# timelapse3fixes.net
KiCad netlist of a schematic drawn in EAGLE
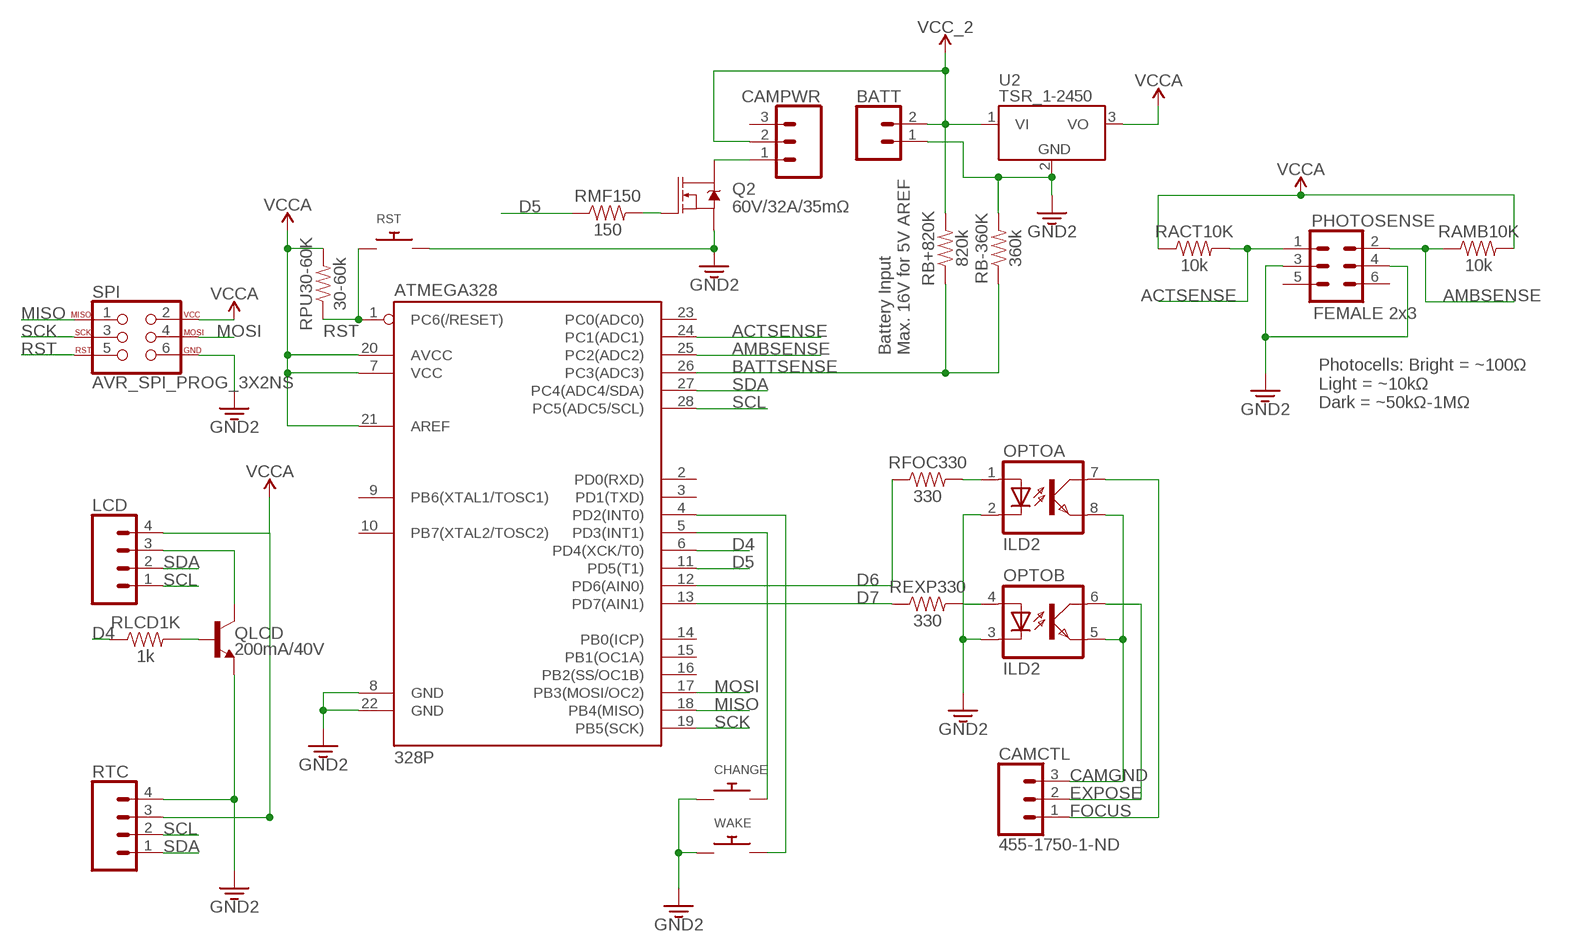
[diagram p0: schematic, sheet 1]

(export (version "E")
  (design (tool "Eeschema 10.0.6"))
  (components
    (comp (ref "ATMEGA328")
      (value "328P")
      (footprint "eagle-import:DIP28")
      (libsource (lib "eagle-import") (part "ATMEGA328P_PDIP"))
    )
    (comp (ref "BATT")
      (value "CONN_02")
      (footprint "eagle-import:1X02")
      (libsource (lib "eagle-import") (part "CONN_02"))
    )
    (comp (ref "CAMCTL")
      (value "455-1750-1-ND")
      (footprint "eagle-import:1X03")
      (libsource (lib "eagle-import") (part "CONN_03"))
    )
    (comp (ref "CAMPWR")
      (value "CONN_03")
      (footprint "eagle-import:1X03")
      (libsource (lib "eagle-import") (part "CONN_03"))
    )
    (comp (ref "CHANGE")
      (value "SWITCH_PUSHBUTTONEVQ-PE")
      (footprint "eagle-import:TACT_PANA-EVQ")
      (libsource (lib "eagle-import") (part "SWITCH_PUSHBUTTONEVQ-PE"))
    )
    (comp (ref "LCD")
      (value "CONN_04")
      (footprint "eagle-import:1X04")
      (libsource (lib "eagle-import") (part "CONN_04"))
    )
    (comp (ref "OPTO")
      (value "ILD2")
      (footprint "eagle-import:DIL08")
      (libsource (lib "eagle-import") (part "ILD2"))
    )
    (comp (ref "PHOTOSENSE")
      (value "FEMALE 2x3")
      (footprint "eagle-import:2X3")
      (libsource (lib "eagle-import") (part "CONN_03X2FEMALE"))
    )
    (comp (ref "Q2")
      (value "60V/32A/35mΩ")
      (footprint "eagle-import:TO220V")
      (libsource (lib "eagle-import") (part "MOSFET-NCH-FQP30N06L"))
    )
    (comp (ref "QLCD")
      (value "200mA/40V")
      (footprint "eagle-import:TO-92")
      (libsource (lib "eagle-import") (part "TRANS_NPN-2N3904"))
    )
    (comp (ref "RACT10K")
      (value "10k")
      (footprint "eagle-import:AXIAL-0.3")
      (libsource (lib "eagle-import") (part "10KOHM-HORIZ-1/4W-1%"))
    )
    (comp (ref "RAMB10K")
      (value "10k")
      (footprint "eagle-import:AXIAL-0.3")
      (libsource (lib "eagle-import") (part "10KOHM-HORIZ-1/4W-1%"))
    )
    (comp (ref "RB+820K")
      (value "820k")
      (footprint "eagle-import:AXIAL-0.3")
      (libsource (lib "eagle-import") (part "10KOHM-HORIZ-1/4W-1%"))
    )
    (comp (ref "RB-360K")
      (value "360k")
      (footprint "eagle-import:AXIAL-0.3")
      (libsource (lib "eagle-import") (part "10KOHM-HORIZ-1/4W-1%"))
    )
    (comp (ref "REXP330")
      (value "330")
      (footprint "eagle-import:AXIAL-0.3")
      (libsource (lib "eagle-import") (part "330OHM-HORIZ-1/10W-5%"))
    )
    (comp (ref "RFOC330")
      (value "330")
      (footprint "eagle-import:AXIAL-0.3")
      (libsource (lib "eagle-import") (part "330OHM-HORIZ-1/10W-5%"))
    )
    (comp (ref "RLCD1K")
      (value "1k")
      (footprint "eagle-import:AXIAL-0.3")
      (libsource (lib "eagle-import") (part "330OHM-HORIZ-1/10W-5%"))
    )
    (comp (ref "RMF150")
      (value "150")
      (footprint "eagle-import:AXIAL-0.3")
      (libsource (lib "eagle-import") (part "330OHM-HORIZ-1/10W-5%"))
    )
    (comp (ref "RPU30-60K")
      (value "30-60k")
      (footprint "eagle-import:AXIAL-0.3")
      (libsource (lib "eagle-import") (part "330OHM-HORIZ-1/10W-5%"))
    )
    (comp (ref "RST")
      (value "SWITCH_PUSHBUTTONEVQ-PE")
      (footprint "eagle-import:TACT_PANA-EVQ")
      (libsource (lib "eagle-import") (part "SWITCH_PUSHBUTTONEVQ-PE"))
    )
    (comp (ref "RTC")
      (value "CONN_04")
      (footprint "eagle-import:1X04")
      (libsource (lib "eagle-import") (part "CONN_04"))
    )
    (comp (ref "SPI")
      (value "AVR_SPI_PROG_3X2NS")
      (footprint "eagle-import:2X3-NS")
      (libsource (lib "eagle-import") (part "AVR_SPI_PROG_3X2NS"))
    )
    (comp (ref "U2")
      (value "TSR_1-2450")
      (footprint "eagle-import:TSR-1")
      (libsource (lib "eagle-import") (part "TSR_1-2450"))
    )
    (comp (ref "WAKE")
      (value "SWITCH_PUSHBUTTONEVQ-PE")
      (footprint "eagle-import:TACT_PANA-EVQ")
      (libsource (lib "eagle-import") (part "SWITCH_PUSHBUTTONEVQ-PE"))
    )
  )
  (nets
    (net (code "1") (name "/ACTSENSE") (class "Default")
      (node (ref "ATMEGA328") (pin "24") (pinfunction "PC1(ADC1)_24") (pintype "bidirectional"))
      (node (ref "PHOTOSENSE") (pin "1") (pinfunction "1_1") (pintype "bidirectional"))
      (node (ref "RACT10K") (pin "P$2") (pinfunction "2_P$2") (pintype "passive"))
    )
    (net (code "2") (name "/AMBSENSE") (class "Default")
      (node (ref "ATMEGA328") (pin "25") (pinfunction "PC2(ADC2)_25") (pintype "bidirectional"))
      (node (ref "PHOTOSENSE") (pin "2") (pinfunction "2_2") (pintype "bidirectional"))
      (node (ref "RAMB10K") (pin "P$1") (pinfunction "1_P$1") (pintype "passive"))
    )
    (net (code "3") (name "/BATTSENSE") (class "Default")
      (node (ref "ATMEGA328") (pin "26") (pinfunction "PC3(ADC3)_26") (pintype "bidirectional"))
      (node (ref "RB+820K") (pin "P$1") (pinfunction "1_P$1") (pintype "passive"))
      (node (ref "RB-360K") (pin "P$1") (pinfunction "1_P$1") (pintype "passive"))
    )
    (net (code "4") (name "/CAMGND") (class "Default")
      (node (ref "CAMCTL") (pin "3") (pinfunction "3_3") (pintype "passive"))
      (node (ref "OPTO") (pin "5") (pinfunction "EMIT_5") (pintype "passive"))
      (node (ref "OPTO") (pin "8") (pinfunction "EMIT_8") (pintype "passive"))
    )
    (net (code "5") (name "/D4") (class "Default")
      (node (ref "ATMEGA328") (pin "6") (pinfunction "PD4(XCK/T0)_6") (pintype "bidirectional"))
      (node (ref "RLCD1K") (pin "P$1") (pinfunction "1_P$1") (pintype "passive"))
    )
    (net (code "6") (name "/D5") (class "Default")
      (node (ref "ATMEGA328") (pin "11") (pinfunction "PD5(T1)_11") (pintype "bidirectional"))
      (node (ref "RMF150") (pin "P$1") (pinfunction "1_P$1") (pintype "passive"))
    )
    (net (code "7") (name "/D6") (class "Default")
      (node (ref "ATMEGA328") (pin "12") (pinfunction "PD6(AIN0)_12") (pintype "bidirectional"))
      (node (ref "RFOC330") (pin "P$1") (pinfunction "1_P$1") (pintype "passive"))
    )
    (net (code "8") (name "/D7") (class "Default")
      (node (ref "ATMEGA328") (pin "13") (pinfunction "PD7(AIN1)_13") (pintype "bidirectional"))
      (node (ref "REXP330") (pin "P$1") (pinfunction "1_P$1") (pintype "passive"))
    )
    (net (code "9") (name "/EXPOSE") (class "Default")
      (node (ref "CAMCTL") (pin "2") (pinfunction "2_2") (pintype "passive"))
      (node (ref "OPTO") (pin "6") (pinfunction "COL_6") (pintype "passive"))
    )
    (net (code "10") (name "/FOCUS") (class "Default")
      (node (ref "CAMCTL") (pin "1") (pinfunction "1_1") (pintype "passive"))
      (node (ref "OPTO") (pin "7") (pinfunction "COL_7") (pintype "passive"))
    )
    (net (code "11") (name "/MISO") (class "Default")
      (node (ref "ATMEGA328") (pin "18") (pinfunction "PB4(MISO)_18") (pintype "bidirectional"))
      (node (ref "SPI") (pin "1") (pinfunction "1_1") (pintype "passive"))
    )
    (net (code "12") (name "/MOSI") (class "Default")
      (node (ref "ATMEGA328") (pin "17") (pinfunction "PB3(MOSI/OC2)_17") (pintype "bidirectional"))
      (node (ref "SPI") (pin "4") (pinfunction "4_4") (pintype "passive"))
    )
    (net (code "13") (name "/RST") (class "Default")
      (node (ref "ATMEGA328") (pin "1") (pinfunction "PC6(/RESET)_1") (pintype "bidirectional"))
      (node (ref "RPU30-60K") (pin "P$1") (pinfunction "1_P$1") (pintype "passive"))
      (node (ref "RST") (pin "P$1") (pinfunction "P$1_P$1") (pintype "passive"))
      (node (ref "SPI") (pin "5") (pinfunction "5_5") (pintype "passive"))
    )
    (net (code "14") (name "/SCK") (class "Default")
      (node (ref "ATMEGA328") (pin "19") (pinfunction "PB5(SCK)_19") (pintype "bidirectional"))
      (node (ref "SPI") (pin "3") (pinfunction "3_3") (pintype "passive"))
    )
    (net (code "15") (name "/SCL") (class "Default")
      (node (ref "ATMEGA328") (pin "28") (pinfunction "PC5(ADC5/SCL)_28") (pintype "bidirectional"))
      (node (ref "LCD") (pin "1") (pinfunction "1_1") (pintype "passive"))
      (node (ref "RTC") (pin "2") (pinfunction "2_2") (pintype "passive"))
    )
    (net (code "16") (name "/SDA") (class "Default")
      (node (ref "ATMEGA328") (pin "27") (pinfunction "PC4(ADC4/SDA)_27") (pintype "bidirectional"))
      (node (ref "LCD") (pin "2") (pinfunction "2_2") (pintype "passive"))
      (node (ref "RTC") (pin "1") (pinfunction "1_1") (pintype "passive"))
    )
    (net (code "17") (name "GND2") (class "Default")
      (node (ref "ATMEGA328") (pin "22") (pinfunction "GND_22") (pintype "bidirectional"))
      (node (ref "ATMEGA328") (pin "8") (pinfunction "GND_8") (pintype "bidirectional"))
      (node (ref "BATT") (pin "1") (pinfunction "1_1") (pintype "passive"))
      (node (ref "CHANGE") (pin "P$1") (pinfunction "P$1_P$1") (pintype "passive"))
      (node (ref "OPTO") (pin "2") (pinfunction "C_2") (pintype "passive"))
      (node (ref "OPTO") (pin "3") (pinfunction "C_3") (pintype "passive"))
      (node (ref "PHOTOSENSE") (pin "3") (pinfunction "3_3") (pintype "bidirectional"))
      (node (ref "PHOTOSENSE") (pin "4") (pinfunction "4_4") (pintype "bidirectional"))
      (node (ref "Q2") (pin "3") (pinfunction "S_3") (pintype "bidirectional"))
      (node (ref "QLCD") (pin "1") (pinfunction "E_1") (pintype "passive"))
      (node (ref "RB-360K") (pin "P$2") (pinfunction "2_P$2") (pintype "passive"))
      (node (ref "RST") (pin "P$2") (pinfunction "P$2_P$2") (pintype "passive"))
      (node (ref "RTC") (pin "4") (pinfunction "4_4") (pintype "passive"))
      (node (ref "SPI") (pin "6") (pinfunction "6_6") (pintype "passive"))
      (node (ref "U2") (pin "2") (pinfunction "GND_2") (pintype "power_in"))
      (node (ref "WAKE") (pin "P$1") (pinfunction "P$1_P$1") (pintype "passive"))
    )
    (net (code "18") (name "Net-(ATMEGA328-PD2(INT0))") (class "Default")
      (node (ref "ATMEGA328") (pin "4") (pinfunction "PD2(INT0)_4") (pintype "bidirectional"))
      (node (ref "WAKE") (pin "P$2") (pinfunction "P$2_P$2") (pintype "passive"))
    )
    (net (code "19") (name "Net-(ATMEGA328-PD3(INT1))") (class "Default")
      (node (ref "ATMEGA328") (pin "5") (pinfunction "PD3(INT1)_5") (pintype "bidirectional"))
      (node (ref "CHANGE") (pin "P$2") (pinfunction "P$2_P$2") (pintype "passive"))
    )
    (net (code "20") (name "Net-(OPTOA-A)") (class "Default")
      (node (ref "OPTO") (pin "1") (pinfunction "A_1") (pintype "passive"))
      (node (ref "RFOC330") (pin "P$2") (pinfunction "2_P$2") (pintype "passive"))
    )
    (net (code "21") (name "Net-(OPTOB-A)") (class "Default")
      (node (ref "OPTO") (pin "4") (pinfunction "A_4") (pintype "passive"))
      (node (ref "REXP330") (pin "P$2") (pinfunction "2_P$2") (pintype "passive"))
    )
    (net (code "22") (name "Net-(Q2-D)") (class "Default")
      (node (ref "CAMPWR") (pin "1") (pinfunction "1_1") (pintype "passive"))
      (node (ref "Q2") (pin "2") (pinfunction "D_2") (pintype "bidirectional"))
    )
    (net (code "23") (name "Net-(Q2-G)") (class "Default")
      (node (ref "Q2") (pin "1") (pinfunction "G_1") (pintype "bidirectional"))
      (node (ref "RMF150") (pin "P$2") (pinfunction "2_P$2") (pintype "passive"))
    )
    (net (code "24") (name "Net-(QLCD-B)") (class "Default")
      (node (ref "QLCD") (pin "2") (pinfunction "B_2") (pintype "passive"))
      (node (ref "RLCD1K") (pin "P$2") (pinfunction "2_P$2") (pintype "passive"))
    )
    (net (code "25") (name "Net-(QLCD-C)") (class "Default")
      (node (ref "LCD") (pin "3") (pinfunction "3_3") (pintype "passive"))
      (node (ref "QLCD") (pin "3") (pinfunction "C_3") (pintype "passive"))
    )
    (net (code "26") (name "VCCA") (class "Default")
      (node (ref "ATMEGA328") (pin "20") (pinfunction "AVCC_20") (pintype "bidirectional"))
      (node (ref "ATMEGA328") (pin "21") (pinfunction "AREF_21") (pintype "bidirectional"))
      (node (ref "ATMEGA328") (pin "7") (pinfunction "VCC_7") (pintype "bidirectional"))
      (node (ref "LCD") (pin "4") (pinfunction "4_4") (pintype "passive"))
      (node (ref "RACT10K") (pin "P$1") (pinfunction "1_P$1") (pintype "passive"))
      (node (ref "RAMB10K") (pin "P$2") (pinfunction "2_P$2") (pintype "passive"))
      (node (ref "RPU30-60K") (pin "P$2") (pinfunction "2_P$2") (pintype "passive"))
      (node (ref "RTC") (pin "3") (pinfunction "3_3") (pintype "passive"))
      (node (ref "SPI") (pin "2") (pinfunction "2_2") (pintype "passive"))
      (node (ref "U2") (pin "3") (pinfunction "VO_3") (pintype "power_in"))
    )
    (net (code "27") (name "VCC_2") (class "Default")
      (node (ref "BATT") (pin "2") (pinfunction "2_2") (pintype "passive"))
      (node (ref "CAMPWR") (pin "2") (pinfunction "2_2") (pintype "passive"))
      (node (ref "RB+820K") (pin "P$2") (pinfunction "2_P$2") (pintype "passive"))
      (node (ref "U2") (pin "1") (pinfunction "VI_1") (pintype "power_in"))
    )
    (net (code "28") (name "unconnected-(ATMEGA328-PB0(ICP)-Pad14)") (class "Default")
      (node (ref "ATMEGA328") (pin "14") (pinfunction "PB0(ICP)_14") (pintype "bidirectional"))
    )
    (net (code "29") (name "unconnected-(ATMEGA328-PB1(OC1A)-Pad15)") (class "Default")
      (node (ref "ATMEGA328") (pin "15") (pinfunction "PB1(OC1A)_15") (pintype "bidirectional"))
    )
    (net (code "30") (name "unconnected-(ATMEGA328-PB2(SS{slash}OC1B)-Pad16)") (class "Default")
      (node (ref "ATMEGA328") (pin "16") (pinfunction "PB2(SS/OC1B)_16") (pintype "bidirectional"))
    )
    (net (code "31") (name "unconnected-(ATMEGA328-PB6(XTAL1{slash}TOSC1)-Pad9)") (class "Default")
      (node (ref "ATMEGA328") (pin "9") (pinfunction "PB6(XTAL1/TOSC1)_9") (pintype "bidirectional"))
    )
    (net (code "32") (name "unconnected-(ATMEGA328-PB7(XTAL2{slash}TOSC2)-Pad10)") (class "Default")
      (node (ref "ATMEGA328") (pin "10") (pinfunction "PB7(XTAL2/TOSC2)_10") (pintype "bidirectional"))
    )
    (net (code "33") (name "unconnected-(ATMEGA328-PC0(ADC0)-Pad23)") (class "Default")
      (node (ref "ATMEGA328") (pin "23") (pinfunction "PC0(ADC0)_23") (pintype "bidirectional"))
    )
    (net (code "34") (name "unconnected-(ATMEGA328-PD0(RXD)-Pad2)") (class "Default")
      (node (ref "ATMEGA328") (pin "2") (pinfunction "PD0(RXD)_2") (pintype "bidirectional"))
    )
    (net (code "35") (name "unconnected-(ATMEGA328-PD1(TXD)-Pad3)") (class "Default")
      (node (ref "ATMEGA328") (pin "3") (pinfunction "PD1(TXD)_3") (pintype "bidirectional"))
    )
    (net (code "36") (name "unconnected-(CAMPWR-Pad3)") (class "Default")
      (node (ref "CAMPWR") (pin "3") (pinfunction "3_3") (pintype "passive"))
    )
    (net (code "37") (name "unconnected-(PHOTOSENSE-Pad5)") (class "Default")
      (node (ref "PHOTOSENSE") (pin "5") (pinfunction "5_5") (pintype "bidirectional"))
    )
    (net (code "38") (name "unconnected-(PHOTOSENSE-Pad6)") (class "Default")
      (node (ref "PHOTOSENSE") (pin "6") (pinfunction "6_6") (pintype "bidirectional"))
    )
  )
)
